# LoadCell_Amp_SCH.net
KiCad netlist of a schematic drawn in Altium Designer
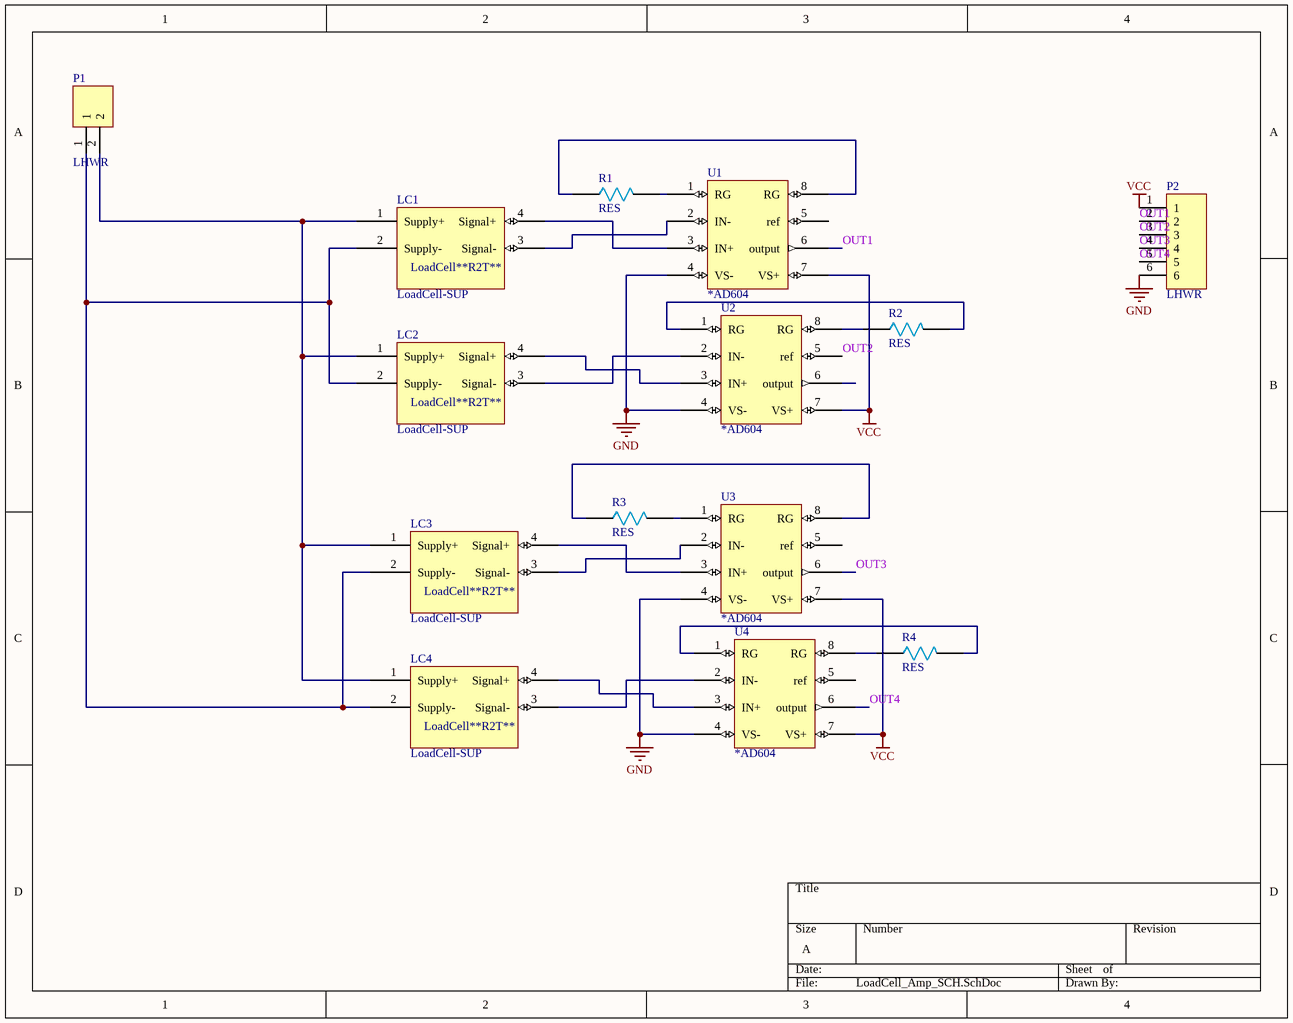
[diagram p0: LoadCell_Amp_SCH.SchDoc]

(export (version "E")
  (design (tool "Eeschema 10.0.6"))
  (components
    (comp (ref "LC1")
      (value "LoadCell-SUP")
      (footprint "LoadCell-SUP")
      (libsource (lib "ES2H_LIB") (part "LoadCell-SUP"))
    )
    (comp (ref "LC2")
      (value "LoadCell-SUP")
      (footprint "LoadCell-SUP")
      (libsource (lib "ES2H_LIB") (part "LoadCell-SUP"))
    )
    (comp (ref "LC3")
      (value "LoadCell-SUP")
      (footprint "LoadCell-SUP")
      (libsource (lib "ES2H_LIB") (part "LoadCell-SUP"))
    )
    (comp (ref "LC4")
      (value "LoadCell-SUP")
      (footprint "LoadCell-SUP")
      (libsource (lib "ES2H_LIB") (part "LoadCell-SUP"))
    )
    (comp (ref "P1")
      (value "LHWR")
      (footprint "Polarized Header 2")
      (fields (field (name "DESIGNER:") "Hamed Jafarzadeh - www.R2T.ir"))
      (libsource (lib "R2T Team Library") (part "2pin LHWR"))
    )
    (comp (ref "P2")
      (value "LHWR")
      (footprint "Polarized Header 6")
      (fields (field (name "DESIGNER:") "Hamed Jafarzadeh - www.R2T.ir"))
      (libsource (lib "R2T Team Library") (part "6pin LHWR"))
    )
    (comp (ref "R1") (value "RES") (footprint "AXIAL0.4") (libsource (lib "MyAltiumLib") (part "RES")))
    (comp (ref "R2") (value "RES") (footprint "AXIAL0.4") (libsource (lib "MyAltiumLib") (part "RES")))
    (comp (ref "R3") (value "RES") (footprint "AXIAL0.4") (libsource (lib "MyAltiumLib") (part "RES")))
    (comp (ref "R4") (value "RES") (footprint "AXIAL0.4") (libsource (lib "MyAltiumLib") (part "RES")))
    (comp (ref "U1")
      (value "*AD604")
      (footprint "AD620-Soic")
      (description "Instrumental Amplifire")
      (libsource (lib "ES2H_LIB") (part "AD620"))
    )
    (comp (ref "U2")
      (value "*AD604")
      (footprint "AD620-Soic")
      (description "Instrumental Amplifire")
      (libsource (lib "ES2H_LIB") (part "AD620"))
    )
    (comp (ref "U3")
      (value "*AD604")
      (footprint "AD620-Soic")
      (description "Instrumental Amplifire")
      (libsource (lib "ES2H_LIB") (part "AD620"))
    )
    (comp (ref "U4")
      (value "*AD604")
      (footprint "AD620-Soic")
      (description "Instrumental Amplifire")
      (libsource (lib "ES2H_LIB") (part "AD620"))
    )
  )
  (nets
    (net (code "1") (name "/OUT1") (class "Default")
      (node (ref "P2") (pin "2") (pinfunction "2_2") (pintype "passive"))
      (node (ref "U1") (pin "6") (pinfunction "output_6") (pintype "output"))
    )
    (net (code "2") (name "/OUT2") (class "Default")
      (node (ref "P2") (pin "3") (pinfunction "3_3") (pintype "passive"))
      (node (ref "U2") (pin "5") (pinfunction "ref_5") (pintype "bidirectional"))
    )
    (net (code "3") (name "/OUT3") (class "Default")
      (node (ref "P2") (pin "4") (pinfunction "4_4") (pintype "passive"))
      (node (ref "U3") (pin "6") (pinfunction "output_6") (pintype "output"))
    )
    (net (code "4") (name "/OUT4") (class "Default")
      (node (ref "P2") (pin "5") (pinfunction "5_5") (pintype "passive"))
      (node (ref "U4") (pin "6") (pinfunction "output_6") (pintype "output"))
    )
    (net (code "5") (name "GND") (class "Default")
      (node (ref "P2") (pin "6") (pinfunction "6_6") (pintype "passive"))
      (node (ref "U1") (pin "4") (pinfunction "VS-_4") (pintype "bidirectional"))
      (node (ref "U2") (pin "4") (pinfunction "VS-_4") (pintype "bidirectional"))
      (node (ref "U3") (pin "4") (pinfunction "VS-_4") (pintype "bidirectional"))
      (node (ref "U4") (pin "4") (pinfunction "VS-_4") (pintype "bidirectional"))
    )
    (net (code "6") (name "Net-(LC1-Signal+)") (class "Default")
      (node (ref "LC1") (pin "4") (pinfunction "Signal+_4") (pintype "bidirectional"))
      (node (ref "U1") (pin "3") (pinfunction "IN+_3") (pintype "bidirectional"))
    )
    (net (code "7") (name "Net-(LC1-Signal-)") (class "Default")
      (node (ref "LC1") (pin "3") (pinfunction "Signal-_3") (pintype "bidirectional"))
      (node (ref "U1") (pin "2") (pinfunction "IN-_2") (pintype "bidirectional"))
    )
    (net (code "8") (name "Net-(LC1-Supply+)") (class "Default")
      (node (ref "LC1") (pin "1") (pinfunction "Supply+_1") (pintype "power_in"))
      (node (ref "LC2") (pin "1") (pinfunction "Supply+_1") (pintype "power_in"))
      (node (ref "LC3") (pin "1") (pinfunction "Supply+_1") (pintype "power_in"))
      (node (ref "LC4") (pin "1") (pinfunction "Supply+_1") (pintype "power_in"))
      (node (ref "P1") (pin "2") (pinfunction "2_2") (pintype "passive"))
    )
    (net (code "9") (name "Net-(LC1-Supply-)") (class "Default")
      (node (ref "LC1") (pin "2") (pinfunction "Supply-_2") (pintype "power_in"))
      (node (ref "LC2") (pin "2") (pinfunction "Supply-_2") (pintype "power_in"))
      (node (ref "LC3") (pin "2") (pinfunction "Supply-_2") (pintype "power_in"))
      (node (ref "LC4") (pin "2") (pinfunction "Supply-_2") (pintype "power_in"))
      (node (ref "P1") (pin "1") (pinfunction "1_1") (pintype "passive"))
    )
    (net (code "10") (name "Net-(LC2-Signal+)") (class "Default")
      (node (ref "LC2") (pin "4") (pinfunction "Signal+_4") (pintype "bidirectional"))
      (node (ref "U2") (pin "3") (pinfunction "IN+_3") (pintype "bidirectional"))
    )
    (net (code "11") (name "Net-(LC2-Signal-)") (class "Default")
      (node (ref "LC2") (pin "3") (pinfunction "Signal-_3") (pintype "bidirectional"))
      (node (ref "U2") (pin "2") (pinfunction "IN-_2") (pintype "bidirectional"))
    )
    (net (code "12") (name "Net-(LC3-Signal+)") (class "Default")
      (node (ref "LC3") (pin "4") (pinfunction "Signal+_4") (pintype "bidirectional"))
      (node (ref "U3") (pin "3") (pinfunction "IN+_3") (pintype "bidirectional"))
    )
    (net (code "13") (name "Net-(LC3-Signal-)") (class "Default")
      (node (ref "LC3") (pin "3") (pinfunction "Signal-_3") (pintype "bidirectional"))
      (node (ref "U3") (pin "2") (pinfunction "IN-_2") (pintype "bidirectional"))
    )
    (net (code "14") (name "Net-(LC4-Signal+)") (class "Default")
      (node (ref "LC4") (pin "4") (pinfunction "Signal+_4") (pintype "bidirectional"))
      (node (ref "U4") (pin "3") (pinfunction "IN+_3") (pintype "bidirectional"))
    )
    (net (code "15") (name "Net-(LC4-Signal-)") (class "Default")
      (node (ref "LC4") (pin "3") (pinfunction "Signal-_3") (pintype "bidirectional"))
      (node (ref "U4") (pin "2") (pinfunction "IN-_2") (pintype "bidirectional"))
    )
    (net (code "16") (name "Net-(R1-Pad1)") (class "Default")
      (node (ref "R1") (pin "1") (pintype "passive"))
      (node (ref "U1") (pin "8") (pinfunction "RG_8") (pintype "bidirectional"))
    )
    (net (code "17") (name "Net-(R1-Pad2)") (class "Default")
      (node (ref "R1") (pin "2") (pintype "passive"))
      (node (ref "U1") (pin "1") (pinfunction "RG_1") (pintype "bidirectional"))
    )
    (net (code "18") (name "Net-(R2-Pad1)") (class "Default")
      (node (ref "R2") (pin "1") (pintype "passive"))
      (node (ref "U2") (pin "8") (pinfunction "RG_8") (pintype "bidirectional"))
    )
    (net (code "19") (name "Net-(R2-Pad2)") (class "Default")
      (node (ref "R2") (pin "2") (pintype "passive"))
      (node (ref "U2") (pin "1") (pinfunction "RG_1") (pintype "bidirectional"))
    )
    (net (code "20") (name "Net-(R3-Pad1)") (class "Default")
      (node (ref "R3") (pin "1") (pintype "passive"))
      (node (ref "U3") (pin "8") (pinfunction "RG_8") (pintype "bidirectional"))
    )
    (net (code "21") (name "Net-(R3-Pad2)") (class "Default")
      (node (ref "R3") (pin "2") (pintype "passive"))
      (node (ref "U3") (pin "1") (pinfunction "RG_1") (pintype "bidirectional"))
    )
    (net (code "22") (name "Net-(R4-Pad1)") (class "Default")
      (node (ref "R4") (pin "1") (pintype "passive"))
      (node (ref "U4") (pin "8") (pinfunction "RG_8") (pintype "bidirectional"))
    )
    (net (code "23") (name "Net-(R4-Pad2)") (class "Default")
      (node (ref "R4") (pin "2") (pintype "passive"))
      (node (ref "U4") (pin "1") (pinfunction "RG_1") (pintype "bidirectional"))
    )
    (net (code "24") (name "VCC") (class "Default")
      (node (ref "P2") (pin "1") (pinfunction "1_1") (pintype "passive"))
      (node (ref "U1") (pin "7") (pinfunction "VS+_7") (pintype "bidirectional"))
      (node (ref "U2") (pin "7") (pinfunction "VS+_7") (pintype "bidirectional"))
      (node (ref "U3") (pin "7") (pinfunction "VS+_7") (pintype "bidirectional"))
      (node (ref "U4") (pin "7") (pinfunction "VS+_7") (pintype "bidirectional"))
    )
    (net (code "25") (name "unconnected-(U1-ref-Pad5)") (class "Default")
      (node (ref "U1") (pin "5") (pinfunction "ref_5") (pintype "bidirectional"))
    )
    (net (code "26") (name "unconnected-(U2-output-Pad6)") (class "Default")
      (node (ref "U2") (pin "6") (pinfunction "output_6") (pintype "output"))
    )
    (net (code "27") (name "unconnected-(U3-ref-Pad5)") (class "Default")
      (node (ref "U3") (pin "5") (pinfunction "ref_5") (pintype "bidirectional"))
    )
    (net (code "28") (name "unconnected-(U4-ref-Pad5)") (class "Default")
      (node (ref "U4") (pin "5") (pinfunction "ref_5") (pintype "bidirectional"))
    )
  )
)
